# QPA9127.net
KiCad netlist of a schematic drawn in Altium Designer
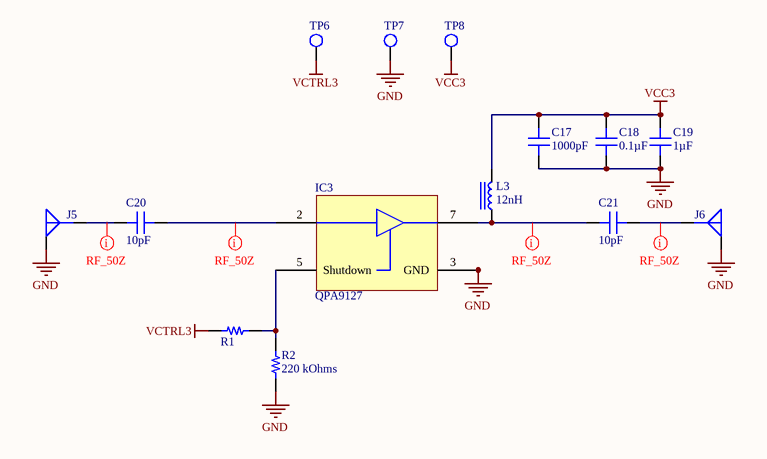
[diagram p0: QPA9127.SchDoc]

(export (version "E")
  (design (tool "Eeschema 10.0.6"))
  (components
    (comp (ref "C17")
      (value "1000pF")
      (footprint "CAP 0402_1005")
      (description "CAP CER 1000PF 50V X7R 0402")
      (fields
        (field (name "PART NUMBER") "GCM155R71H102KA37D")
        (field (name "MANUFACTURER") "Murata Electronics")
      )
      (libsource (lib "Celestial Altium Library - altium_library") (part "Capacitor"))
    )
    (comp (ref "C18")
      (value "0.1µF")
      (footprint "CAP 0402_1005")
      (description "CAP CER 0.1UF 16V X7R 0402")
      (fields (field (name "PART NUMBER") "EMK105B7104KV-F") (field (name "MANUFACTURER") "Taiyo Yuden"))
      (libsource (lib "Celestial Altium Library - altium_library") (part "Capacitor"))
    )
    (comp (ref "C19")
      (value "1µF")
      (footprint "CAP 0402_1005")
      (description "CAP CER 1UF 10V X5R 0402")
      (fields
        (field (name "PART NUMBER") "CL05A105KP5NNNC")
        (field (name "MANUFACTURER") "Samsung Electro-Mechanics")
      )
      (libsource (lib "Celestial Altium Library - altium_library") (part "Capacitor"))
    )
    (comp (ref "C20")
      (value "10pF")
      (footprint "CAP 0402_1005 RF")
      (description "CAP CER 10PF 50V C0G/NP0 0402")
      (fields
        (field (name "PART NUMBER") "GJM1555C1H100FB01D")
        (field (name "MANUFACTURER") "Murata Electronics")
      )
      (libsource (lib "Celestial Altium Library - altium_library") (part "Capacitor"))
    )
    (comp (ref "C21")
      (value "10pF")
      (footprint "CAP 0402_1005 RF")
      (description "CAP CER 10PF 50V C0G/NP0 0402")
      (fields
        (field (name "PART NUMBER") "GJM1555C1H100FB01D")
        (field (name "MANUFACTURER") "Murata Electronics")
      )
      (libsource (lib "Celestial Altium Library - altium_library") (part "Capacitor"))
    )
    (comp (ref "IC3")
      (value "QPA9127")
      (footprint "Qorvo PA DFN-8 2X2")
      (description "High Linearity Gain Block")
      (libsource (lib "IC") (part "QPA9127"))
    )
    (comp (ref "J5")
      (value "CON-SMA-EDGE-S")
      (footprint "CON-SMA-EDGE-S")
      (description "CONN SMA JACK STR EDGE MNT")
      (libsource (lib "Connector") (part "CON-SMA-EDGE-S"))
    )
    (comp (ref "J6")
      (value "CON-SMA-EDGE-S")
      (footprint "CON-SMA-EDGE-S")
      (description "CONN SMA JACK STR EDGE MNT")
      (libsource (lib "Connector") (part "CON-SMA-EDGE-S"))
    )
    (comp (ref "L3")
      (value "12nH")
      (footprint "0603HP")
      (description "Fixed Inductors 0603 12nH Unshld 2% 1.1A 88mOhms")
      (libsource (lib "Inductor") (part "0603HP-12NXGLW"))
    )
    (comp (ref "R1")
      (value "~")
      (footprint "RES 0402_1005")
      (description "RES SMD 0 OHM JUMPER 1/16W 0402")
      (fields (field (name "PART NUMBER") "RC0402JR-070RP") (field (name "MANUFACTURER") "Yageo"))
      (libsource (lib "Celestial Altium Library - altium_library") (part "Resistor"))
    )
    (comp (ref "R2")
      (value "220 kOhms")
      (footprint "RES 0402_1005")
      (description "RES SMD 220K OHM 1% 1/16W 0402")
      (fields (field (name "PART NUMBER") "RC0402FR-07220KL") (field (name "MANUFACTURER") "Yageo"))
      (libsource (lib "Celestial Altium Library - altium_library") (part "Resistor"))
    )
    (comp (ref "TP6")
      (value "Test Point-THM")
      (footprint "KEYSTONE-THM-TestPoint")
      (description "THRU HOLE MOUNT TEST POINTS")
      (libsource (lib "Misc") (part "Test Point-THM"))
    )
    (comp (ref "TP7")
      (value "Test Point-THM")
      (footprint "KEYSTONE-THM-TestPoint")
      (description "THRU HOLE MOUNT TEST POINTS")
      (libsource (lib "Misc") (part "Test Point-THM"))
    )
    (comp (ref "TP8")
      (value "Test Point-THM")
      (footprint "KEYSTONE-THM-TestPoint")
      (description "THRU HOLE MOUNT TEST POINTS")
      (libsource (lib "Misc") (part "Test Point-THM"))
    )
  )
  (nets
    (net (code "1") (name "GND") (class "Default")
      (node (ref "C17") (pin "1") (pinfunction "1_1") (pintype "passive"))
      (node (ref "C18") (pin "1") (pinfunction "1_1") (pintype "passive"))
      (node (ref "C19") (pin "1") (pinfunction "1_1") (pintype "passive"))
      (node (ref "IC3") (pin "1") (pinfunction "GND_1") (pintype "passive"))
      (node (ref "IC3") (pin "3") (pinfunction "GND_3") (pintype "passive"))
      (node (ref "IC3") (pin "4") (pinfunction "GND_4") (pintype "passive"))
      (node (ref "IC3") (pin "6") (pinfunction "GND_6") (pintype "passive"))
      (node (ref "IC3") (pin "8") (pinfunction "GND_8") (pintype "passive"))
      (node (ref "IC3") (pin "9") (pinfunction "GND_9") (pintype "passive"))
      (node (ref "J5") (pin "2") (pinfunction "G_2") (pintype "passive"))
      (node (ref "J6") (pin "2") (pinfunction "G_2") (pintype "passive"))
      (node (ref "R2") (pin "1") (pinfunction "1_1") (pintype "passive"))
      (node (ref "TP7") (pin "1") (pinfunction "TP_1") (pintype "passive"))
    )
    (net (code "2") (name "Net-(IC3-IN)") (class "Default")
      (node (ref "C20") (pin "2") (pinfunction "2_2") (pintype "passive"))
      (node (ref "IC3") (pin "2") (pinfunction "IN_2") (pintype "passive"))
    )
    (net (code "3") (name "Net-(IC3-OUT)") (class "Default")
      (node (ref "C21") (pin "1") (pinfunction "1_1") (pintype "passive"))
      (node (ref "IC3") (pin "7") (pinfunction "OUT_7") (pintype "passive"))
      (node (ref "L3") (pin "1") (pinfunction "1_1") (pintype "passive"))
    )
    (net (code "4") (name "Net-(IC3-Shutdown)") (class "Default")
      (node (ref "IC3") (pin "5") (pinfunction "Shutdown_5") (pintype "passive"))
      (node (ref "R1") (pin "2") (pinfunction "2_2") (pintype "passive"))
      (node (ref "R2") (pin "2") (pinfunction "2_2") (pintype "passive"))
    )
    (net (code "5") (name "Net-(J5-S)") (class "Default")
      (node (ref "C20") (pin "1") (pinfunction "1_1") (pintype "passive"))
      (node (ref "J5") (pin "1") (pinfunction "S_1") (pintype "passive"))
    )
    (net (code "6") (name "Net-(J6-S)") (class "Default")
      (node (ref "C21") (pin "2") (pinfunction "2_2") (pintype "passive"))
      (node (ref "J6") (pin "1") (pinfunction "S_1") (pintype "passive"))
    )
    (net (code "7") (name "VCC3") (class "Default")
      (node (ref "C17") (pin "2") (pinfunction "2_2") (pintype "passive"))
      (node (ref "C18") (pin "2") (pinfunction "2_2") (pintype "passive"))
      (node (ref "C19") (pin "2") (pinfunction "2_2") (pintype "passive"))
      (node (ref "L3") (pin "2") (pinfunction "2_2") (pintype "passive"))
      (node (ref "TP8") (pin "1") (pinfunction "TP_1") (pintype "passive"))
    )
    (net (code "8") (name "VCTRL3") (class "Default")
      (node (ref "R1") (pin "1") (pinfunction "1_1") (pintype "passive"))
      (node (ref "TP6") (pin "1") (pinfunction "TP_1") (pintype "passive"))
    )
  )
)
